# barra_sec_principal.net
KiCad netlist of a schematic drawn in Altium Designer
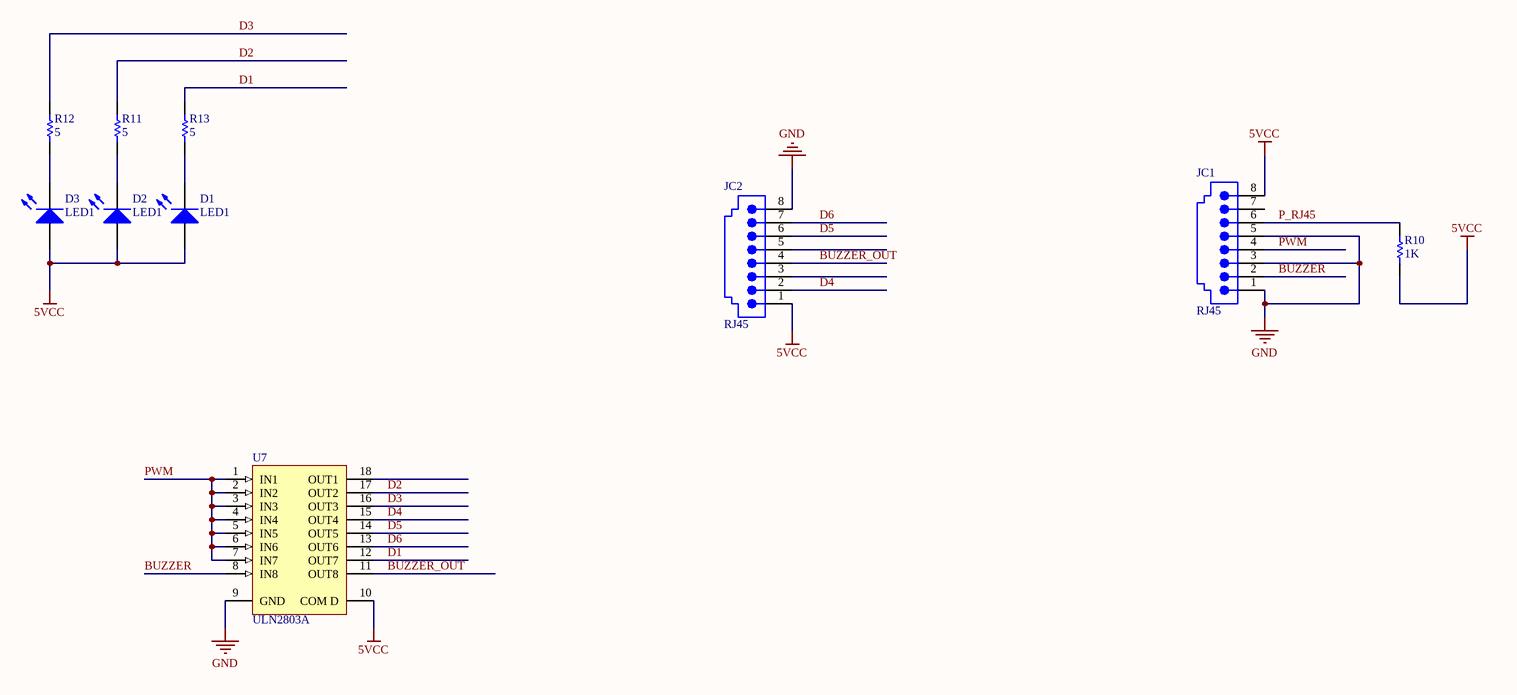
[diagram p0: barra_sec_principal.SchDoc]

(export (version "E")
  (design (tool "Eeschema 10.0.6"))
  (components
    (comp (ref "D1")
      (value "LED1")
      (footprint "LED5MM RED")
      (description "Typical RED GaAs LED")
      (fields (field (name "PUBLISHER") "Altium Limited"))
      (libsource (lib "Miscellaneous Devices") (part "LED1"))
    )
    (comp (ref "D2")
      (value "LED1")
      (footprint "LED5MM RED")
      (description "Typical RED GaAs LED")
      (fields (field (name "PUBLISHER") "Altium Limited"))
      (libsource (lib "Miscellaneous Devices") (part "LED1"))
    )
    (comp (ref "D3")
      (value "LED1")
      (footprint "LED5MM RED")
      (description "Typical RED GaAs LED")
      (fields (field (name "PUBLISHER") "Altium Limited"))
      (libsource (lib "Miscellaneous Devices") (part "LED1"))
    )
    (comp (ref "JC1")
      (value "RJ45")
      (footprint "15-43-6233")
      (description "Right Angle, Standard Profile, RJ45-Keyed, Flange Mount PCB Jack")
      (fields (field (name "PUBLISHER") "Altium Limited"))
      (libsource (lib "Molex Modular Jack Right Angle") (part "15-43-6233"))
    )
    (comp (ref "JC2")
      (value "RJ45")
      (footprint "15-43-6233")
      (description "Right Angle, Standard Profile, RJ45-Keyed, Flange Mount PCB Jack")
      (fields (field (name "PUBLISHER") "Altium Limited"))
      (libsource (lib "Molex Modular Jack Right Angle") (part "15-43-6233"))
    )
    (comp (ref "R10")
      (value "1K")
      (footprint "AXIAL-0.3")
      (description "Resistor")
      (fields (field (name "Comment") "Res") (field (name "PUBLISHER") "Altium Limited"))
      (libsource (lib "Miscellaneous Devices") (part "Res1"))
    )
    (comp (ref "R11")
      (value "5")
      (footprint "AXIAL-0.3")
      (description "Resistor")
      (fields (field (name "Comment") "Res") (field (name "PUBLISHER") "Altium Limited"))
      (libsource (lib "Miscellaneous Devices") (part "Res1"))
    )
    (comp (ref "R12")
      (value "5")
      (footprint "AXIAL-0.3")
      (description "Resistor")
      (fields (field (name "Comment") "Res") (field (name "PUBLISHER") "Altium Limited"))
      (libsource (lib "Miscellaneous Devices") (part "Res1"))
    )
    (comp (ref "R13")
      (value "5")
      (footprint "AXIAL-0.3")
      (description "Resistor")
      (fields (field (name "Comment") "Res") (field (name "PUBLISHER") "Altium Limited"))
      (libsource (lib "Miscellaneous Devices") (part "Res1"))
    )
    (comp (ref "U7")
      (value "ULN2803A")
      (footprint "A18")
      (description "High-Voltage, High-Current Darlington Array")
      (fields (field (name "PUBLISHER") "Altium Limited"))
      (libsource (lib "Allegro Interface Darlington Driver") (part "ULN2803A"))
    )
  )
  (nets
    (net (code "1") (name "/BUZZER") (class "Default")
      (node (ref "JC1") (pin "2") (pinfunction "2_2") (pintype "passive"))
      (node (ref "U7") (pin "8") (pinfunction "IN8_8") (pintype "input"))
    )
    (net (code "2") (name "/BUZZER_OUT") (class "Default")
      (node (ref "JC2") (pin "4") (pinfunction "4_4") (pintype "passive"))
      (node (ref "U7") (pin "11") (pinfunction "OUT8_11") (pintype "open_collector"))
    )
    (net (code "3") (name "/D1") (class "Default")
      (node (ref "R13") (pin "2") (pinfunction "2_2") (pintype "passive"))
      (node (ref "U7") (pin "12") (pinfunction "OUT7_12") (pintype "open_collector"))
    )
    (net (code "4") (name "/D2") (class "Default")
      (node (ref "R11") (pin "2") (pinfunction "2_2") (pintype "passive"))
      (node (ref "U7") (pin "17") (pinfunction "OUT2_17") (pintype "open_collector"))
    )
    (net (code "5") (name "/D3") (class "Default")
      (node (ref "R12") (pin "2") (pinfunction "2_2") (pintype "passive"))
      (node (ref "U7") (pin "16") (pinfunction "OUT3_16") (pintype "open_collector"))
    )
    (net (code "6") (name "/D4") (class "Default")
      (node (ref "JC2") (pin "2") (pinfunction "2_2") (pintype "passive"))
      (node (ref "U7") (pin "15") (pinfunction "OUT4_15") (pintype "open_collector"))
    )
    (net (code "7") (name "/D5") (class "Default")
      (node (ref "JC2") (pin "6") (pinfunction "6_6") (pintype "passive"))
      (node (ref "U7") (pin "14") (pinfunction "OUT5_14") (pintype "open_collector"))
    )
    (net (code "8") (name "/D6") (class "Default")
      (node (ref "JC2") (pin "7") (pinfunction "7_7") (pintype "passive"))
      (node (ref "U7") (pin "13") (pinfunction "OUT6_13") (pintype "open_collector"))
    )
    (net (code "9") (name "/PWM") (class "Default")
      (node (ref "JC1") (pin "4") (pinfunction "4_4") (pintype "passive"))
      (node (ref "U7") (pin "1") (pinfunction "IN1_1") (pintype "input"))
      (node (ref "U7") (pin "2") (pinfunction "IN2_2") (pintype "input"))
      (node (ref "U7") (pin "3") (pinfunction "IN3_3") (pintype "input"))
      (node (ref "U7") (pin "4") (pinfunction "IN4_4") (pintype "input"))
      (node (ref "U7") (pin "5") (pinfunction "IN5_5") (pintype "input"))
      (node (ref "U7") (pin "6") (pinfunction "IN6_6") (pintype "input"))
      (node (ref "U7") (pin "7") (pinfunction "IN7_7") (pintype "input"))
    )
    (net (code "10") (name "/P_RJ45") (class "Default")
      (node (ref "JC1") (pin "6") (pinfunction "6_6") (pintype "passive"))
      (node (ref "R10") (pin "2") (pinfunction "2_2") (pintype "passive"))
    )
    (net (code "11") (name "5VCC") (class "Default")
      (node (ref "D1") (pin "1") (pinfunction "A_1") (pintype "passive"))
      (node (ref "D2") (pin "1") (pinfunction "A_1") (pintype "passive"))
      (node (ref "D3") (pin "1") (pinfunction "A_1") (pintype "passive"))
      (node (ref "JC1") (pin "8") (pinfunction "8_8") (pintype "passive"))
      (node (ref "JC2") (pin "1") (pinfunction "1_1") (pintype "passive"))
      (node (ref "R10") (pin "1") (pinfunction "1_1") (pintype "passive"))
      (node (ref "U7") (pin "10") (pinfunction "COM_D_10") (pintype "passive"))
    )
    (net (code "12") (name "GND") (class "Default")
      (node (ref "JC1") (pin "1") (pinfunction "1_1") (pintype "passive"))
      (node (ref "JC1") (pin "3") (pinfunction "3_3") (pintype "passive"))
      (node (ref "JC1") (pin "5") (pinfunction "5_5") (pintype "passive"))
      (node (ref "JC2") (pin "8") (pinfunction "8_8") (pintype "passive"))
      (node (ref "U7") (pin "9") (pinfunction "GND_9") (pintype "power_in"))
    )
    (net (code "13") (name "Net-(D1-K)") (class "Default")
      (node (ref "D1") (pin "2") (pinfunction "K_2") (pintype "passive"))
      (node (ref "R13") (pin "1") (pinfunction "1_1") (pintype "passive"))
    )
    (net (code "14") (name "Net-(D2-K)") (class "Default")
      (node (ref "D2") (pin "2") (pinfunction "K_2") (pintype "passive"))
      (node (ref "R11") (pin "1") (pinfunction "1_1") (pintype "passive"))
    )
    (net (code "15") (name "Net-(D3-K)") (class "Default")
      (node (ref "D3") (pin "2") (pinfunction "K_2") (pintype "passive"))
      (node (ref "R12") (pin "1") (pinfunction "1_1") (pintype "passive"))
    )
    (net (code "16") (name "unconnected-(JC1-Pad7)") (class "Default")
      (node (ref "JC1") (pin "7") (pinfunction "7_7") (pintype "passive"))
    )
    (net (code "17") (name "unconnected-(JC2-Pad3)") (class "Default")
      (node (ref "JC2") (pin "3") (pinfunction "3_3") (pintype "passive"))
    )
    (net (code "18") (name "unconnected-(JC2-Pad5)") (class "Default")
      (node (ref "JC2") (pin "5") (pinfunction "5_5") (pintype "passive"))
    )
    (net (code "19") (name "unconnected-(U7-OUT1-Pad18)") (class "Default")
      (node (ref "U7") (pin "18") (pinfunction "OUT1_18") (pintype "open_collector"))
    )
  )
)
